# OpenArt.net
KiCad netlist of a schematic drawn in EasyEDA Pro
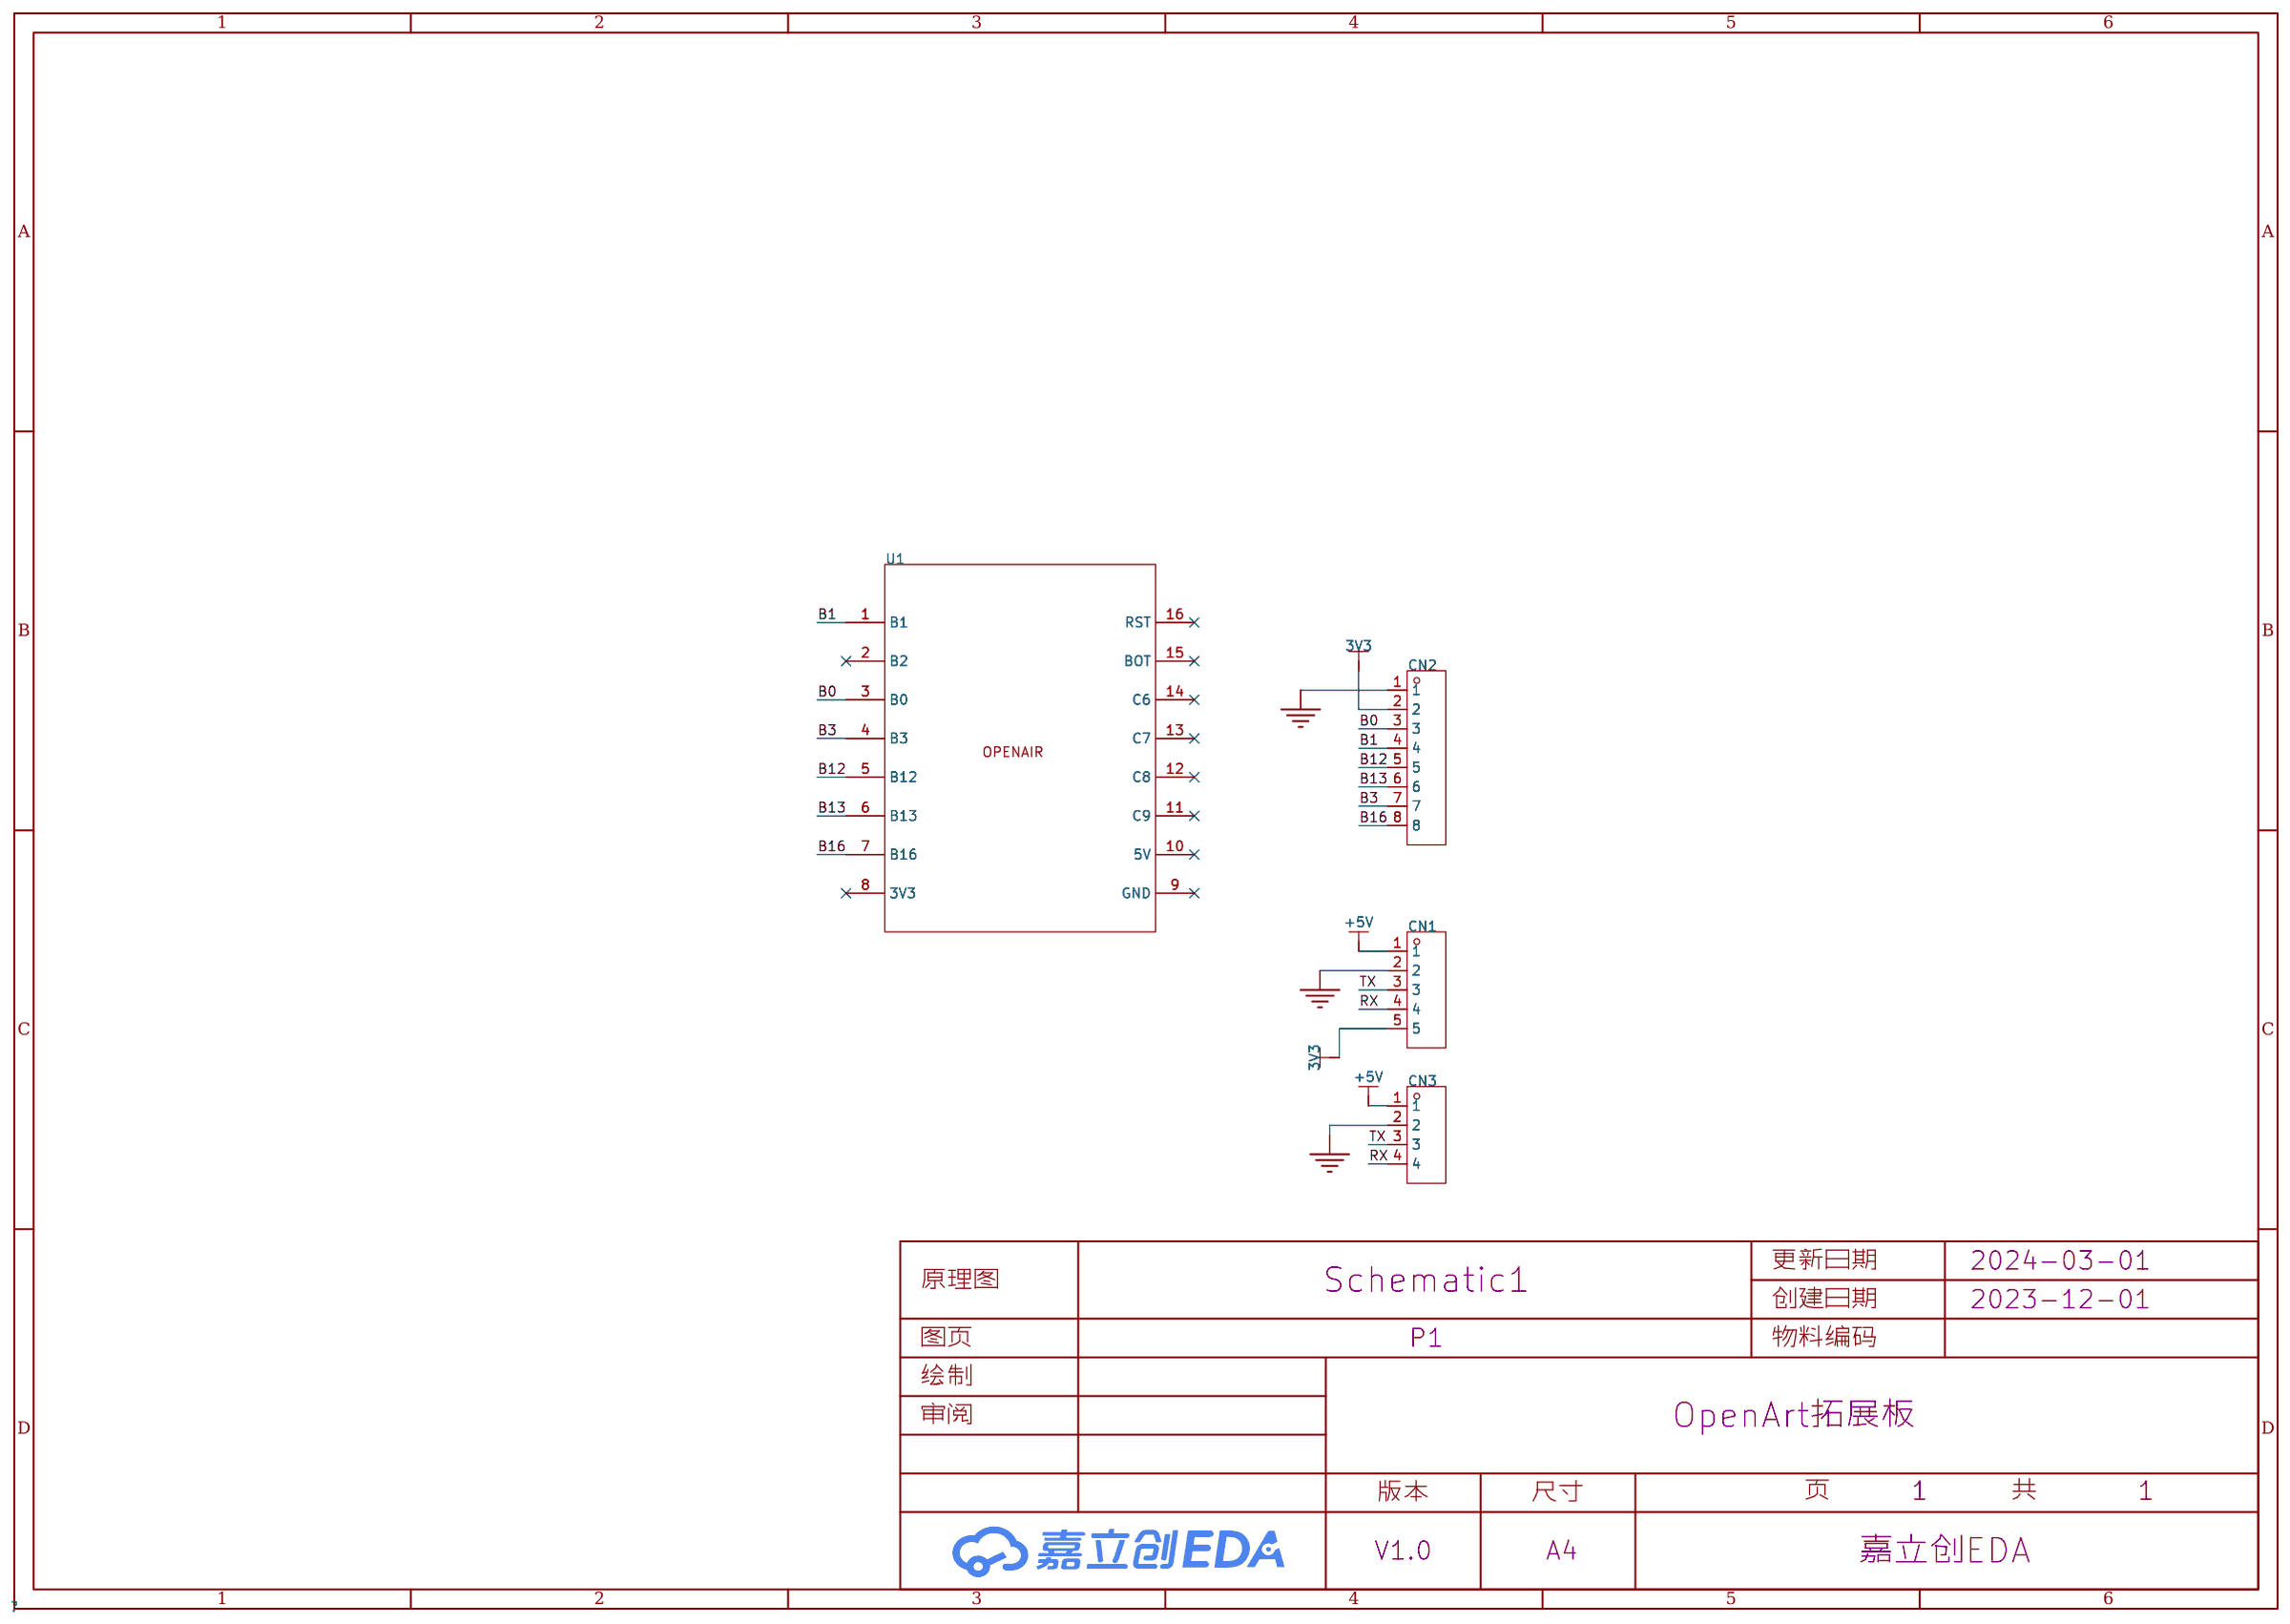
[diagram p0: schematic sheet]

(export (version "E")
  (design (tool "Eeschema 10.0.6"))
  (components
    (comp (ref "CN1")
      (value "ZX-HA2.54-5PWZ")
      (footprint "easyedapro:CONN-TH_5P-P2.50_ZX-HA2.54-5PWZ")
      (fields (field (name "Manufacturer") "Megastar(兆星)"))
      (libsource (lib "easyedapro") (part "ZX-HA2.54-5PWZ"))
    )
    (comp (ref "CN2")
      (value "BX-XH2.54-8PZZ")
      (footprint "easyedapro:CONN-TH_8P-P2.50_BX-XH2.54-8PZZ")
      (fields (field (name "Manufacturer") "Bossie(博锡)"))
      (libsource (lib "easyedapro") (part "BX-XH2.54-8PZZ"))
    )
    (comp (ref "CN3")
      (value "ZX-XH2.54-4PWZ")
      (footprint "easyedapro:CONN-TH_4P-P2.50_ZX-XH2.54-4PWZ")
      (fields (field (name "Manufacturer") "Megastar(兆星)"))
      (libsource (lib "easyedapro") (part "ZX-XH2.54-4PWZ"))
    )
    (comp (ref "U1") (value "~") (libsource (lib "easyedapro") (part "OPENAIR")))
  )
  (nets
    (net (code "1") (name "+5V") (class "Default")
      (node (ref "CN1") (pin "1") (pinfunction "1_1") (pintype "unspecified"))
      (node (ref "CN3") (pin "1") (pinfunction "1_1") (pintype "unspecified"))
    )
    (net (code "2") (name "/B0") (class "Default")
      (node (ref "CN2") (pin "3") (pinfunction "3_3") (pintype "unspecified"))
      (node (ref "U1") (pin "3") (pinfunction "B0_3") (pintype "input"))
    )
    (net (code "3") (name "/B1") (class "Default")
      (node (ref "CN2") (pin "4") (pinfunction "4_4") (pintype "unspecified"))
      (node (ref "U1") (pin "1") (pinfunction "B1_1") (pintype "input"))
    )
    (net (code "4") (name "/B3") (class "Default")
      (node (ref "CN2") (pin "7") (pinfunction "7_7") (pintype "unspecified"))
      (node (ref "U1") (pin "4") (pinfunction "B3_4") (pintype "input"))
    )
    (net (code "5") (name "/B12") (class "Default")
      (node (ref "CN2") (pin "5") (pinfunction "5_5") (pintype "unspecified"))
      (node (ref "U1") (pin "5") (pinfunction "B12_5") (pintype "input"))
    )
    (net (code "6") (name "/B13") (class "Default")
      (node (ref "CN2") (pin "6") (pinfunction "6_6") (pintype "unspecified"))
      (node (ref "U1") (pin "6") (pinfunction "B13_6") (pintype "input"))
    )
    (net (code "7") (name "/B16") (class "Default")
      (node (ref "CN2") (pin "8") (pinfunction "8_8") (pintype "unspecified"))
      (node (ref "U1") (pin "7") (pinfunction "B16_7") (pintype "input"))
    )
    (net (code "8") (name "/RX") (class "Default")
      (node (ref "CN1") (pin "4") (pinfunction "4_4") (pintype "unspecified"))
      (node (ref "CN3") (pin "4") (pinfunction "4_4") (pintype "unspecified"))
    )
    (net (code "9") (name "/TX") (class "Default")
      (node (ref "CN1") (pin "3") (pinfunction "3_3") (pintype "unspecified"))
      (node (ref "CN3") (pin "3") (pinfunction "3_3") (pintype "unspecified"))
    )
    (net (code "10") (name "3V3") (class "Default")
      (node (ref "CN1") (pin "5") (pinfunction "5_5") (pintype "unspecified"))
      (node (ref "CN2") (pin "2") (pinfunction "2_2") (pintype "unspecified"))
    )
    (net (code "11") (name "GND") (class "Default")
      (node (ref "CN1") (pin "2") (pinfunction "2_2") (pintype "unspecified"))
      (node (ref "CN2") (pin "1") (pinfunction "1_1") (pintype "unspecified"))
      (node (ref "CN3") (pin "2") (pinfunction "2_2") (pintype "unspecified"))
    )
    (net (code "12") (name "unconnected-(U1-3V3-Pad8)") (class "Default")
      (node (ref "U1") (pin "8") (pinfunction "3V3_8") (pintype "input+no_connect"))
    )
    (net (code "13") (name "unconnected-(U1-5V-Pad10)") (class "Default")
      (node (ref "U1") (pin "10") (pinfunction "5V_10") (pintype "input+no_connect"))
    )
    (net (code "14") (name "unconnected-(U1-B2-Pad2)") (class "Default")
      (node (ref "U1") (pin "2") (pinfunction "B2_2") (pintype "input+no_connect"))
    )
    (net (code "15") (name "unconnected-(U1-BOT-Pad15)") (class "Default")
      (node (ref "U1") (pin "15") (pinfunction "BOT_15") (pintype "input+no_connect"))
    )
    (net (code "16") (name "unconnected-(U1-C6-Pad14)") (class "Default")
      (node (ref "U1") (pin "14") (pinfunction "C6_14") (pintype "input+no_connect"))
    )
    (net (code "17") (name "unconnected-(U1-C7-Pad13)") (class "Default")
      (node (ref "U1") (pin "13") (pinfunction "C7_13") (pintype "input+no_connect"))
    )
    (net (code "18") (name "unconnected-(U1-C8-Pad12)") (class "Default")
      (node (ref "U1") (pin "12") (pinfunction "C8_12") (pintype "input+no_connect"))
    )
    (net (code "19") (name "unconnected-(U1-C9-Pad11)") (class "Default")
      (node (ref "U1") (pin "11") (pinfunction "C9_11") (pintype "input+no_connect"))
    )
    (net (code "20") (name "unconnected-(U1-GND-Pad9)") (class "Default")
      (node (ref "U1") (pin "9") (pinfunction "GND_9") (pintype "input+no_connect"))
    )
    (net (code "21") (name "unconnected-(U1-RST-Pad16)") (class "Default")
      (node (ref "U1") (pin "16") (pinfunction "RST_16") (pintype "input+no_connect"))
    )
  )
)
